# Sheet1.net
KiCad netlist of a schematic drawn in Altium Designer
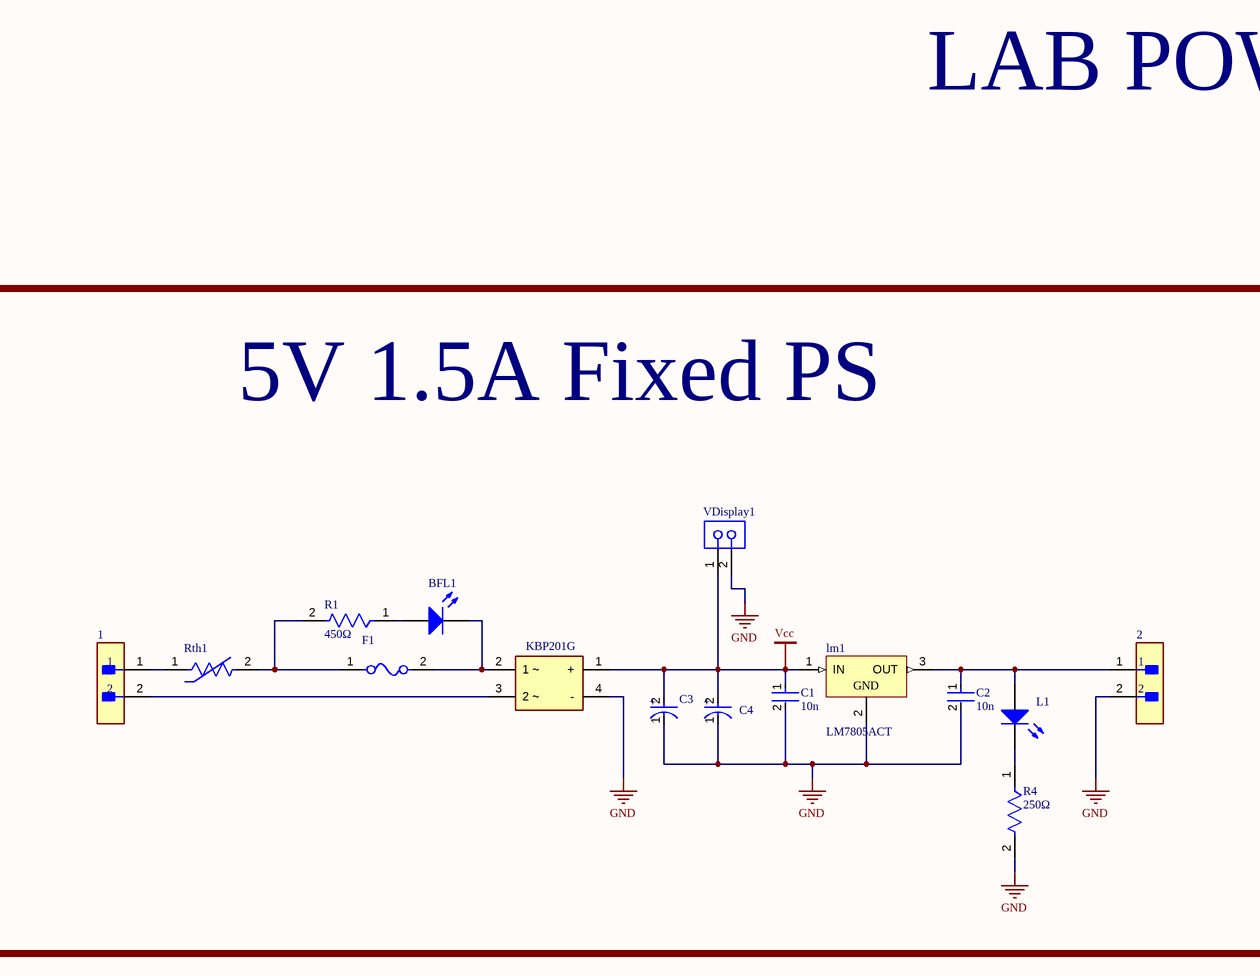
[diagram p0: Sheet1.SchDoc, top left]
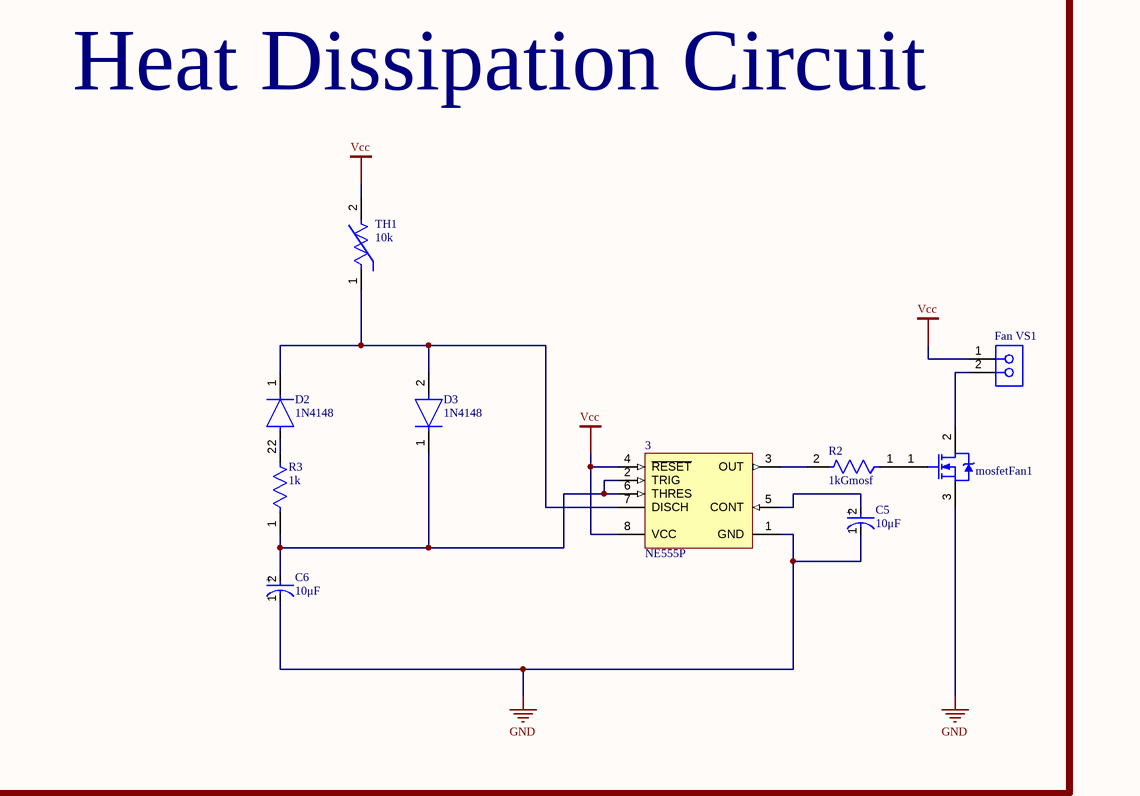
[diagram p1: Sheet1.SchDoc, top right]
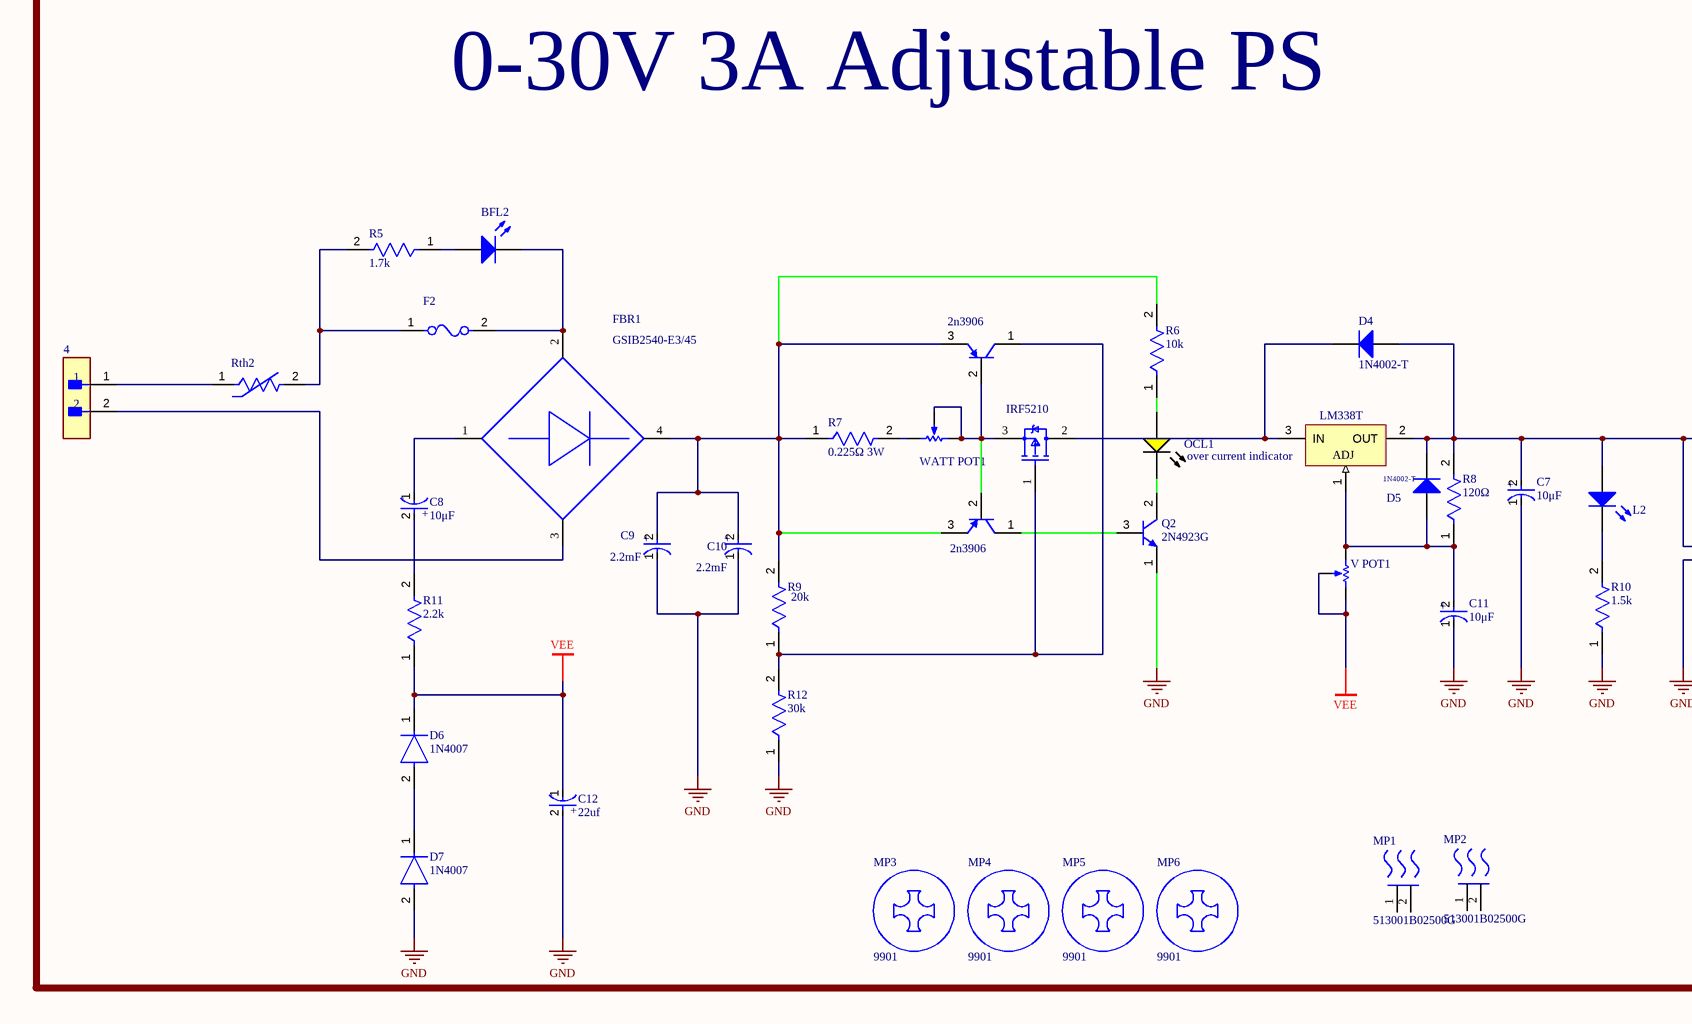
[diagram p2: Sheet1.SchDoc, bottom left]
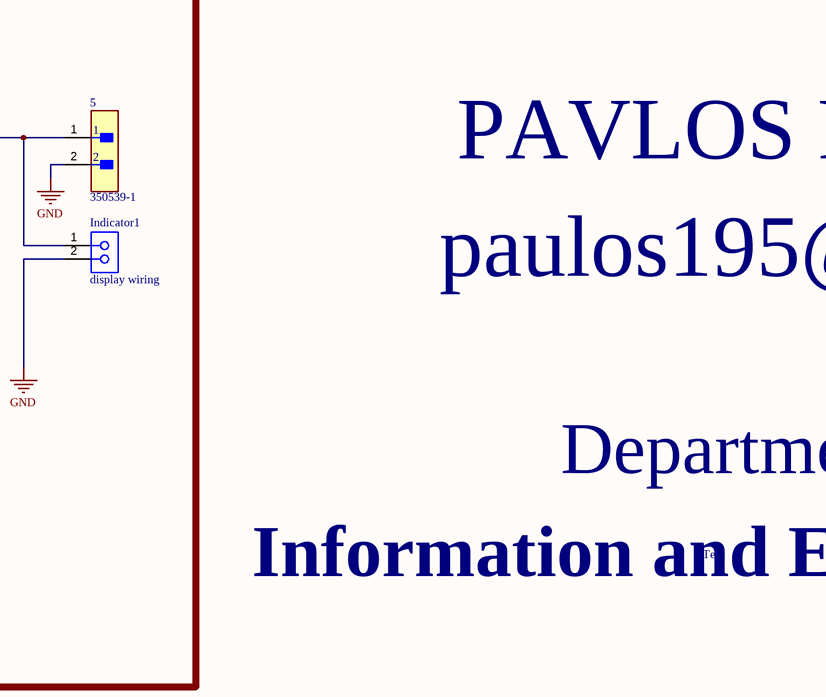
[diagram p3: Sheet1.SchDoc, bottom right]

(export (version "E")
  (design (tool "Eeschema 10.0.6"))
  (components
    (comp (ref "1")
      (value "350539-1")
      (footprint "FP-350539-1-MFG")
      (description "CONN HEADER VERT 2POS 5.08MM")
      (fields
        (field (name "MANUFACTURER") "TE Connectivity")
        (field (name "OCTOPART") "https://octopart.com/350539-1-te+connectivity-46510628")
      )
      (libsource (lib "Altium Content Vault") (part "3bc925449376181038e59eaffc5286c"))
    )
    (comp (ref "2")
      (value "350539-1")
      (footprint "FP-350539-1-MFG")
      (description "CONN HEADER VERT 2POS 5.08MM")
      (fields
        (field (name "MANUFACTURER") "TE Connectivity")
        (field (name "OCTOPART") "https://octopart.com/350539-1-te+connectivity-46510628")
      )
      (libsource (lib "") (part "3bc925449376181038e59eaffc5286c_1"))
    )
    (comp (ref "3")
      (value "NE555P")
      (footprint "P0008A")
      (description "Precision Timer, 4.5 to 16 V, 0 to 70 degC, 8-Pin DIP, Pb-Free, Tube")
      (fields (field (name "MANUFACTURER") "TexasInstruments"))
      (libsource (lib "Altium Content Vault") (part "TI-NE555-P8"))
    )
    (comp (ref "4")
      (value "350539-1")
      (footprint "FP-350539-1-MFG")
      (description "CONN HEADER VERT 2POS 5.08MM")
      (fields
        (field (name "MANUFACTURER") "TE Connectivity")
        (field (name "OCTOPART") "https://octopart.com/350539-1-te+connectivity-46510628")
      )
      (libsource (lib "Altium Content Vault") (part "3bc925449376181038e59eaffc5286c"))
    )
    (comp (ref "5")
      (value "350539-1")
      (footprint "FP-350539-1-MFG")
      (description "CONN HEADER VERT 2POS 5.08MM")
      (fields
        (field (name "MANUFACTURER") "TE Connectivity")
        (field (name "OCTOPART") "https://octopart.com/350539-1-te+connectivity-46510628")
      )
      (libsource (lib "") (part "3bc925449376181038e59eaffc5286c_1"))
    )
    (comp (ref "BFL1")
      (value "Blowfuse indicator")
      (footprint "Type 3mm")
      (description "THT LED round mono-color color lens, WL-TMRW, Super Red")
      (fields (field (name "PARTNUMBER") "151031SS04000") (field (name "MANUFACTURER") "Wuerth Elektronik"))
      (libsource (lib "Altium Content Vault") (part "WE-LED_K1A2-2"))
    )
    (comp (ref "BFL2")
      (value "Blown fuse indicator")
      (footprint "Type 3mm")
      (description "THT LED round mono-color color lens, WL-TMRW, Super Red")
      (fields (field (name "PARTNUMBER") "151031SS04000") (field (name "MANUFACTURER") "Wuerth Elektronik"))
      (libsource (lib "Altium Content Vault") (part "WE-LED_K1A2-2"))
    )
    (comp (ref "C1")
      (value "10n")
      (footprint "FP-RDE0M1-MFG")
      (description "Ceramic Capacitor 100nF ±10% 50V X7R Radial")
      (fields (field (name "TOLERANCE") "10%"))
      (libsource (lib "Altium Content Vault") (part "b4654b650e69147ec39a6b967a45e02"))
    )
    (comp (ref "C2")
      (value "10n")
      (footprint "FP-RDE0M1-MFG")
      (description "Ceramic Capacitor 100nF ±10% 50V X7R Radial")
      (fields (field (name "TOLERANCE") "10%"))
      (libsource (lib "Altium Content Vault") (part "b4654b650e69147ec39a6b967a45e02"))
    )
    (comp (ref "C3")
      (value "2.2mF")
      (footprint "FP-EGPA500ELL222ML40S-MFG")
      (description "CAP ALUM 2200UF 20% 50V RADIAL")
      (fields (field (name "VOLTAGE") "50V") (field (name "TOLERANCE") "20%"))
      (libsource (lib "Altium Content Vault") (part "cf48714ba7e38822c1575c7ec0b6d1f"))
    )
    (comp (ref "C4")
      (value "2.2mF")
      (footprint "FP-EGPA500ELL222ML40S-MFG")
      (description "CAP ALUM 2200UF 20% 50V RADIAL")
      (fields (field (name "VOLTAGE") "50V") (field (name "TOLERANCE") "20%"))
      (libsource (lib "Altium Content Vault") (part "cf48714ba7e38822c1575c7ec0b6d1f"))
    )
    (comp (ref "C5")
      (value "10μF")
      (footprint "FP-ECA-2CHG010I-MFG")
      (description "CAP ALUM 1UF 20% 160V RADIAL")
      (fields (field (name "TOLERANCE") "20%"))
      (libsource (lib "Altium Content Vault") (part "a00bbbee19879c290e62620ae7e47b1"))
    )
    (comp (ref "C6")
      (value "10μF")
      (footprint "FP-ECA-2CHG010I-MFG")
      (description "CAP ALUM 1UF 20% 160V RADIAL")
      (fields (field (name "TOLERANCE") "20%"))
      (libsource (lib "Altium Content Vault") (part "a00bbbee19879c290e62620ae7e47b1"))
    )
    (comp (ref "C7")
      (value "10μF")
      (footprint "FP-ECA-2CHG010I-MFG")
      (description "CAP ALUM 1UF 20% 160V RADIAL")
      (fields (field (name "TOLERANCE") "20%"))
      (libsource (lib "Altium Content Vault") (part "a00bbbee19879c290e62620ae7e47b1"))
    )
    (comp (ref "C8")
      (value "10μF")
      (footprint "FP-ECA-2CHG010I-MFG")
      (description "CAP ALUM 1UF 20% 160V RADIAL")
      (fields (field (name "TOLERANCE") "20%"))
      (libsource (lib "Altium Content Vault") (part "a00bbbee19879c290e62620ae7e47b1"))
    )
    (comp (ref "C9")
      (value "2.2mF")
      (footprint "FP-EGPA500ELL222ML40S-MFG")
      (description "CAP ALUM 2200UF 20% 50V RADIAL")
      (fields (field (name "VOLTAGE") "50V") (field (name "TOLERANCE") "20%"))
      (libsource (lib "Altium Content Vault") (part "cf48714ba7e38822c1575c7ec0b6d1f"))
    )
    (comp (ref "C10")
      (value "2.2mF")
      (footprint "FP-EGPA500ELL222ML40S-MFG")
      (description "CAP ALUM 2200UF 20% 50V RADIAL")
      (fields (field (name "VOLTAGE") "50V") (field (name "TOLERANCE") "20%"))
      (libsource (lib "Altium Content Vault") (part "cf48714ba7e38822c1575c7ec0b6d1f"))
    )
    (comp (ref "C11")
      (value "10μF")
      (footprint "FP-ECA-2CHG010I-MFG")
      (description "CAP ALUM 1UF 20% 160V RADIAL")
      (fields (field (name "TOLERANCE") "20%"))
      (libsource (lib "Altium Content Vault") (part "a00bbbee19879c290e62620ae7e47b1"))
    )
    (comp (ref "C12")
      (value "22uf")
      (footprint "FP-RAD-TH-D_5_0_5-L_7_1-F-MFG")
      (description "Aluminum Electrolytic Capacitors (Radial Lead Type) 33uF ±20% 10V")
      (fields (field (name "TOLERANCE") "20%") (field (name "VOLTAGE") "10V"))
      (libsource (lib "Altium Content Vault") (part "a00bbbee19879c290e62620ae7e47b1"))
    )
    (comp (ref "D1")
      (value "KBP201G")
      (footprint "FP-KBP-MFG")
      (description "BRIDGE RECT 1PHASE 600V 2A KBP")
      (fields
        (field (name "OCTOPART") "https://octopart.com/kbp206g-diodes+inc.-330175")
        (field (name "MANUFACTURER") "Diodes Inc.")
      )
      (libsource (lib "Altium Content Vault") (part "3a1086ec435a8680de2aa37bc9d9ffa"))
    )
    (comp (ref "D2")
      (value "1N4148")
      (footprint "FP-017AG-MFG")
      (description "DIODE GEN PURP 100V 200MA DO35")
      (fields (field (name "VOLTAGE") "100V"))
      (libsource (lib "Altium Content Vault") (part "d7152d700b627762746794eb795d46e"))
    )
    (comp (ref "D3")
      (value "1N4148")
      (footprint "FP-017AG-MFG")
      (description "DIODE GEN PURP 100V 200MA DO35")
      (fields (field (name "VOLTAGE") "100V"))
      (libsource (lib "Altium Content Vault") (part "d7152d700b627762746794eb795d46e"))
    )
    (comp (ref "D4")
      (value "1N4002-T")
      (footprint "DIOD-DO-41-P-2_V")
      (description "1.0 A Rectifier, 15 pF, 100 V, -65 to 150 degC, 2-Pin DO-41 Plastic, RoHS, Tape and Reel")
      (fields (field (name "MANUFACTURER") "Diodes Inc"))
      (libsource (lib "Altium Content Vault") (part "DIOD-D-A1K2-2"))
    )
    (comp (ref "D5")
      (value "1N4002-T")
      (footprint "DIOD-DO-41-P-2_V")
      (description "1.0 A Rectifier, 15 pF, 100 V, -65 to 150 degC, 2-Pin DO-41 Plastic, RoHS, Tape and Reel")
      (fields (field (name "MANUFACTURER") "Diodes Inc"))
      (libsource (lib "Altium Content Vault") (part "DIOD-D-A1K2-2"))
    )
    (comp (ref "D6")
      (value "1N4007")
      (footprint "FP-1N4007-MFG")
      (description "Rectifier diode 1000 V 1 A DO-41, ,")
      (fields
        (field (name "MANUFACTURER") "Diotec")
        (field (name "OCTOPART") "https://octopart.com/1n4007-diotec-4040411")
      )
      (libsource (lib "Altium Content Vault") (part "d7152d700b627762746794eb795d46e"))
    )
    (comp (ref "D7")
      (value "1N4007")
      (footprint "FP-1N4007-MFG")
      (description "Rectifier diode 1000 V 1 A DO-41, ,")
      (fields
        (field (name "MANUFACTURER") "Diotec")
        (field (name "OCTOPART") "https://octopart.com/1n4007-diotec-4040411")
      )
      (libsource (lib "Altium Content Vault") (part "d7152d700b627762746794eb795d46e"))
    )
    (comp (ref "F1")
      (value "64600001223")
      (footprint "FP-64600001223-MFG")
      (description "FUSE BLOCK CART 250V 6.3A PCB")
      (fields
        (field (name "MANUFACTURER") "Littelfuse Inc")
        (field (name "OCTOPART") "https://octopart.com/64600001223-littelfuse-39645661")
      )
      (libsource (lib "Altium Content Vault") (part "5bcf9b9f640e542cf0359d10258e979"))
    )
    (comp (ref "F2")
      (value "64600001223")
      (footprint "FP-64600001223-MFG")
      (description "FUSE BLOCK CART 250V 6.3A PCB")
      (fields
        (field (name "MANUFACTURER") "Littelfuse Inc")
        (field (name "OCTOPART") "https://octopart.com/64600001223-littelfuse-39645661")
      )
      (libsource (lib "Altium Content Vault") (part "5bcf9b9f640e542cf0359d10258e979"))
    )
    (comp (ref "Fan VS1")
      (value "SSQ-102-01-G-S")
      (footprint "SMTC-SSQ-102-01-X-S")
      (description "SQ Post Socket, Through-hole, Vertical, -55 to 125 degC, 2.54 mm Pitch, 2-Pin, Female, RoHS")
      (fields (field (name "MANUFACTURER") "Samtec"))
      (libsource (lib "Altium Content Vault") (part "SMTC-SSQ-102-01-X-S"))
    )
    (comp (ref "FBR1")
      (value "GSIB2540-E3/45")
      (footprint "FP-GSIB2580-E3-45-MFG")
      (description "BRIDGE RECT 1P 800V 3.5A GSIB-5S")
      (fields (field (name "VOLTAGE") "200V"))
      (libsource (lib "Altium Content Vault") (part "51aac32ad35959c46097de5ad95dde1"))
    )
    (comp (ref "Indicator1")
      (value "display wiring")
      (footprint "SMTC-SSQ-102-01-X-S")
      (description "SQ Post Socket, Through-hole, Vertical, -55 to 125 degC, 2.54 mm Pitch, 2-Pin, Female, RoHS")
      (fields (field (name "PARTNUMBER") "SSQ-102-01-G-S") (field (name "MANUFACTURER") "Samtec"))
      (libsource (lib "Altium Content Vault") (part "SMTC-SSQ-102-01-X-S"))
    )
    (comp (ref "L1")
      (value "on indicator")
      (footprint "Type 3mm")
      (description "THT LED round mono-color color lens, WL-TMRC , Bright Green")
      (fields (field (name "PARTNUMBER") "151031VS06000") (field (name "MANUFACTURER") "Wuerth Elektronik"))
      (libsource (lib "Altium Content Vault") (part "WE-LED_K1A2-2"))
    )
    (comp (ref "L2")
      (value "on indicator")
      (footprint "Type 3mm")
      (description "THT LED round mono-color color lens, WL-TMRC , Bright Green")
      (fields (field (name "PARTNUMBER") "151031VS06000") (field (name "MANUFACTURER") "Wuerth Elektronik"))
      (libsource (lib "Altium Content Vault") (part "WE-LED_K1A2-2"))
    )
    (comp (ref "lm1")
      (value "LM7805ACT")
      (footprint "FAIR-TO-220-3")
      (description "Positive Voltage Regulator, 5 V, 1 A, 0 to 125 degC, 3-Pin TO-220, RoHS, Tube")
      (fields (field (name "MANUFACTURER") "Fairchild"))
      (libsource (lib "Altium Content Vault") (part "FAIR-LM7805CT-TO220-3"))
    )
    (comp (ref "LM2")
      (value "LM338T")
      (footprint "NDE0003A")
      (description "5 Amp Adjustable Regulator, 3-pin TO-220, Pb-Free")
      (fields (field (name "MANUFACTURER") "Texas Instruments"))
      (libsource (lib "Altium Content Vault") (part "PM-REG-LM1086ADJ-SIL3"))
    )
    (comp (ref "mosfetCL1")
      (value "IRF5210")
      (footprint "FP-PG-TO262-3-MFG")
      (description "MOSFET P-CH 100V 38A TO262")
      (libsource (lib "Altium Content Vault") (part "6d22d991b1185862a08a901caf23a14"))
    )
    (comp (ref "mosfetFan1")
      (value "IRF3205PBF")
      (footprint "INF-PG-TO-220AB")
      (description "HEXFET(R) Power N-Channel MOSFET, 55 V, 110 A, -55 to 117 degC, 3-Pin TO-220AB, RoHS, Rail/Tube")
      (fields (field (name "MANUFACTURER") "International Rectifier"))
      (libsource (lib "Altium Content Vault") (part "NEMOS-GDS-3_B"))
    )
    (comp (ref "MP1")
      (value "513001B02500G")
      (footprint "FP-513001B02500G-MFG")
      (description "BOARD LEVEL HEAT SINK")
      (libsource (lib "Altium Content Vault") (part "2bc51668f00a2e820a271c5c65feed3"))
    )
    (comp (ref "MP2")
      (value "513001B02500G")
      (footprint "FP-513001B02500G-MFG")
      (description "BOARD LEVEL HEAT SINK")
      (libsource (lib "Altium Content Vault") (part "2bc51668f00a2e820a271c5c65feed3"))
    )
    (comp (ref "MP3")
      (value "9901")
      (footprint "FP-9901-MFG")
      (description "MACHINE SCREW PAN PHILLIPS 4-40")
      (libsource (lib "Altium Content Vault") (part "00aa4b1e0213c22a4cfa0708b50314e"))
    )
    (comp (ref "MP4")
      (value "9901")
      (footprint "FP-9901-MFG")
      (description "MACHINE SCREW PAN PHILLIPS 4-40")
      (libsource (lib "Altium Content Vault") (part "00aa4b1e0213c22a4cfa0708b50314e"))
    )
    (comp (ref "MP5")
      (value "9901")
      (footprint "FP-9901-MFG")
      (description "MACHINE SCREW PAN PHILLIPS 4-40")
      (libsource (lib "Altium Content Vault") (part "00aa4b1e0213c22a4cfa0708b50314e"))
    )
    (comp (ref "MP6")
      (value "9901")
      (footprint "FP-9901-MFG")
      (description "MACHINE SCREW PAN PHILLIPS 4-40")
      (libsource (lib "Altium Content Vault") (part "00aa4b1e0213c22a4cfa0708b50314e"))
    )
    (comp (ref "OCL1")
      (value "over current indicator")
      (footprint "KING-WP7113SYD_V")
      (description "The Super Bright Yellow Device, 2 V, -40 to 85 degC, 2-Pin THD, RoHS, Tape and Reel")
      (fields (field (name "TOLERANCE") "1%"))
      (libsource (lib "Altium Content Vault") (part "LED-YELLOW-AK-2"))
    )
    (comp (ref "Q1")
      (value "2n3906")
      (footprint "ONSC-TO-92-3-29-11_AM_BL")
      (description "Amplifier Transistor, PNP Silicon, 3-Pin TO-92, Pb-Free, Tape and Reel BC557BRL1G")
      (fields (field (name "MANUFACTURER") "On Semiconductor") (field (name "PARTNUMBER") "BC557BRL1G"))
      (libsource (lib "Altium Content Vault") (part "ONSC-PNP-C1B2E3-3"))
    )
    (comp (ref "Q2")
      (value "2N4923G")
      (footprint "ONSC-TO-225-3-77-09")
      (description "Medium-Power Plastic NPN Silicon Transistor, 3-Pin TO-225, Pb-Free, Bulk Box")
      (fields (field (name "MANUFACTURER") "On Semiconductor"))
      (libsource (lib "Altium Content Vault") (part "ONSC-NPN-E1C2B3-3"))
    )
    (comp (ref "Q3")
      (value "2n3906")
      (footprint "ONSC-TO-92-3-29-11_AM_BL")
      (description "Amplifier Transistor, PNP Silicon, 3-Pin TO-92, Pb-Free, Tape and Reel")
      (fields (field (name "MANUFACTURER") "On Semiconductor") (field (name "PARTNUMBER") "BC557BRL1G"))
      (libsource (lib "Altium Content Vault") (part "ONSC-PNP-C1B2E3-3"))
    )
    (comp (ref "R1")
      (value "450Ω")
      (footprint "FP-CF14-MFG")
      (description "RES 7.5K OHM 1/4W 5% AXIAL")
      (fields (field (name "TOLERANCE") "5%"))
      (libsource (lib "Altium Content Vault") (part "1029c3af85768c4190bb7ad29bc67b5"))
    )
    (comp (ref "R2")
      (value "1kGmosf")
      (footprint "FP-CF14-MFG")
      (description "RES 7.5K OHM 1/4W 5% AXIAL")
      (fields (field (name "TOLERANCE") "5%"))
      (libsource (lib "Altium Content Vault") (part "1029c3af85768c4190bb7ad29bc67b5"))
    )
    (comp (ref "R3")
      (value "1k")
      (footprint "FP-CF14-MFG")
      (description "RES 7.5K OHM 1/4W 5% AXIAL")
      (fields (field (name "TOLERANCE") "5%"))
      (libsource (lib "Altium Content Vault") (part "1029c3af85768c4190bb7ad29bc67b5"))
    )
    (comp (ref "R4")
      (value "250Ω")
      (footprint "FP-CF14-MFG")
      (description "RES 7.5K OHM 1/4W 5% AXIAL")
      (fields (field (name "TOLERANCE") "5%"))
      (libsource (lib "Altium Content Vault") (part "1029c3af85768c4190bb7ad29bc67b5"))
    )
    (comp (ref "R5")
      (value "1.7k")
      (footprint "FP-CF14-MFG")
      (description "RES 7.5K OHM 1/4W 5% AXIAL")
      (fields (field (name "TOLERANCE") "5%"))
      (libsource (lib "Altium Content Vault") (part "1029c3af85768c4190bb7ad29bc67b5"))
    )
    (comp (ref "R6")
      (value "10k")
      (footprint "FP-CF14-MFG")
      (description "RES 7.5K OHM 1/4W 5% AXIAL")
      (fields (field (name "TOLERANCE") "5%"))
      (libsource (lib "Altium Content Vault") (part "1029c3af85768c4190bb7ad29bc67b5"))
    )
    (comp (ref "R7")
      (value "0.225Ω 3W")
      (footprint "FP-PAC03-MFG")
      (description "RES 560 OHM 3W 1% AXIAL")
      (fields (field (name "TOLERANCE") "1%"))
      (libsource (lib "Altium Content Vault") (part "1029c3af85768c4190bb7ad29bc67b5"))
    )
    (comp (ref "R8")
      (value "120Ω")
      (footprint "FP-CF14-MFG")
      (description "RES 7.5K OHM 1/4W 5% AXIAL")
      (fields (field (name "TOLERANCE") "5%"))
      (libsource (lib "Altium Content Vault") (part "1029c3af85768c4190bb7ad29bc67b5"))
    )
    (comp (ref "R9")
      (value "20k")
      (footprint "FP-CF14-MFG")
      (description "RES 7.5K OHM 1/4W 5% AXIAL")
      (fields (field (name "TOLERANCE") "5%"))
      (libsource (lib "Altium Content Vault") (part "1029c3af85768c4190bb7ad29bc67b5"))
    )
    (comp (ref "R10")
      (value "1.5k")
      (footprint "FP-CF14-MFG")
      (description "RES 7.5K OHM 1/4W 5% AXIAL")
      (fields (field (name "TOLERANCE") "5%"))
      (libsource (lib "Altium Content Vault") (part "1029c3af85768c4190bb7ad29bc67b5"))
    )
    (comp (ref "R11")
      (value "2.2k")
      (footprint "FP-CF14-MFG")
      (description "RES 7.5K OHM 1/4W 5% AXIAL")
      (fields (field (name "TOLERANCE") "5%"))
      (libsource (lib "Altium Content Vault") (part "1029c3af85768c4190bb7ad29bc67b5"))
    )
    (comp (ref "R12")
      (value "30k")
      (footprint "FP-CF14-MFG")
      (description "RES 7.5K OHM 1/4W 5% AXIAL")
      (fields (field (name "TOLERANCE") "5%"))
      (libsource (lib "Altium Content Vault") (part "1029c3af85768c4190bb7ad29bc67b5"))
    )
    (comp (ref "Rth1")
      (value "NTPAA5R1LDNB0")
      (footprint "FP-NTPAA-MFG")
      (description "ICL 5.1 OHM 15% 2.5A 10MM")
      (fields (field (name "TOLERANCE") "15%") (field (name "VOLTAGE") "264V"))
      (libsource (lib "Altium Content Vault") (part "3b148a6ebabc5fb4d708a66c052d352"))
    )
    (comp (ref "Rth2")
      (value "NTPAA5R1LDNB0")
      (footprint "FP-NTPAA-MFG")
      (description "ICL 5.1 OHM 15% 2.5A 10MM")
      (fields (field (name "TOLERANCE") "15%") (field (name "VOLTAGE") "264V"))
      (libsource (lib "Altium Content Vault") (part "3b148a6ebabc5fb4d708a66c052d352"))
    )
    (comp (ref "TH1")
      (value "10k")
      (footprint "FP-103AT-2-MFG")
      (description "Thermistor NTC 10KOhm 1% 2-Pin")
      (fields (field (name "TOLERANCE") "1%"))
      (libsource (lib "Altium Content Vault") (part "3b148a6ebabc5fb4d708a66c052d352"))
    )
    (comp (ref "V POT1")
      (value "2.85k")
      (footprint "BOUR-3852A-282-103AL-3_V")
      (description "Diameter Panel Control, 10 KOhm, +/- 10%, 2 W, -1 to 125 degC, 3-Pin THD, RoHS, Bulk")
      (fields (field (name "TOLERANCE") "±10%") (field (name "MANUFACTURER") "Bourns"))
      (libsource (lib "Altium Content Vault") (part "RES-POT-3"))
    )
    (comp (ref "VDisplay1")
      (value "SSQ-102-01-G-S")
      (footprint "SMTC-SSQ-102-01-X-S")
      (description "SQ Post Socket, Through-hole, Vertical, -55 to 125 degC, 2.54 mm Pitch, 2-Pin, Female, RoHS")
      (fields (field (name "MANUFACTURER") "Samtec"))
      (libsource (lib "Altium Content Vault") (part "SMTC-SSQ-102-01-X-S"))
    )
    (comp (ref "WATT POT1")
      (value "3852A-282-103AL")
      (footprint "BOUR-3852A-282-103AL-3_V")
      (description "Diameter Panel Control, 10 KOhm, +/- 10%, 2 W, -1 to 125 degC, 3-Pin THD, RoHS, Bulk")
      (fields (field (name "TOLERANCE") "±10%") (field (name "MANUFACTURER") "Bourns"))
      (libsource (lib "Altium Content Vault") (part "RES-POT-3"))
    )
  )
  (nets
    (net (code "1") (name "GND") (class "Default")
      (node (ref "2") (pin "2") (pinfunction "2_2") (pintype "passive"))
      (node (ref "3") (pin "1") (pinfunction "GND_1") (pintype "power_in"))
      (node (ref "5") (pin "2") (pinfunction "2_2") (pintype "passive"))
      (node (ref "C1") (pin "2") (pinfunction "2_2") (pintype "passive"))
      (node (ref "C10") (pin "1") (pinfunction "C_1") (pintype "passive"))
      (node (ref "C11") (pin "1") (pinfunction "C_1") (pintype "passive"))
      (node (ref "C12") (pin "2") (pinfunction "A_2") (pintype "passive"))
      (node (ref "C2") (pin "2") (pinfunction "2_2") (pintype "passive"))
      (node (ref "C3") (pin "1") (pinfunction "C_1") (pintype "passive"))
      (node (ref "C4") (pin "1") (pinfunction "C_1") (pintype "passive"))
      (node (ref "C5") (pin "1") (pinfunction "C_1") (pintype "passive"))
      (node (ref "C6") (pin "1") (pinfunction "C_1") (pintype "passive"))
      (node (ref "C7") (pin "1") (pinfunction "C_1") (pintype "passive"))
      (node (ref "C9") (pin "1") (pinfunction "C_1") (pintype "passive"))
      (node (ref "D1") (pin "4") (pinfunction "-_4") (pintype "passive"))
      (node (ref "D7") (pin "2") (pinfunction "A_2") (pintype "passive"))
      (node (ref "Indicator1") (pin "2") (pinfunction "2_2") (pintype "passive"))
      (node (ref "Q2") (pin "1") (pinfunction "E_1") (pintype "passive"))
      (node (ref "R10") (pin "1") (pinfunction "1_1") (pintype "passive"))
      (node (ref "R12") (pin "1") (pinfunction "1_1") (pintype "passive"))
      (node (ref "R4") (pin "2") (pinfunction "2_2") (pintype "passive"))
      (node (ref "VDisplay1") (pin "2") (pinfunction "2_2") (pintype "passive"))
      (node (ref "lm1") (pin "2") (pinfunction "GND_2") (pintype "power_in"))
      (node (ref "mosfetFan1") (pin "3") (pinfunction "S_3") (pintype "passive"))
    )
    (net (code "2") (name "Net-(1-Pad1)") (class "Default")
      (node (ref "1") (pin "1") (pinfunction "1_1") (pintype "passive"))
      (node (ref "Rth1") (pin "1") (pinfunction "1_1") (pintype "passive"))
    )
    (net (code "3") (name "Net-(3-CONT)") (class "Default")
      (node (ref "3") (pin "5") (pinfunction "CONT_5") (pintype "input"))
      (node (ref "C5") (pin "2") (pinfunction "A_2") (pintype "passive"))
    )
    (net (code "4") (name "Net-(3-DISCH)") (class "Default")
      (node (ref "3") (pin "7") (pinfunction "DISCH_7") (pintype "open_collector"))
      (node (ref "D2") (pin "1") (pinfunction "C_1") (pintype "passive"))
      (node (ref "D3") (pin "2") (pinfunction "A_2") (pintype "passive"))
      (node (ref "TH1") (pin "1") (pinfunction "1_1") (pintype "passive"))
    )
    (net (code "5") (name "Net-(3-OUT)") (class "Default")
      (node (ref "3") (pin "3") (pinfunction "OUT_3") (pintype "output"))
      (node (ref "R2") (pin "2") (pinfunction "2_2") (pintype "passive"))
    )
    (net (code "6") (name "Net-(3-THRES)") (class "Default")
      (node (ref "3") (pin "2") (pinfunction "TRIG_2") (pintype "input"))
      (node (ref "3") (pin "6") (pinfunction "THRES_6") (pintype "input"))
      (node (ref "C6") (pin "2") (pinfunction "A_2") (pintype "passive"))
      (node (ref "D3") (pin "1") (pinfunction "C_1") (pintype "passive"))
      (node (ref "R3") (pin "1") (pinfunction "1_1") (pintype "passive"))
    )
    (net (code "7") (name "Net-(4-Pad1)") (class "Default")
      (node (ref "4") (pin "1") (pinfunction "1_1") (pintype "passive"))
      (node (ref "Rth2") (pin "1") (pinfunction "1_1") (pintype "passive"))
    )
    (net (code "8") (name "Net-(BFL1-A)") (class "Default")
      (node (ref "BFL1") (pin "2") (pinfunction "A_2") (pintype "passive"))
      (node (ref "R1") (pin "1") (pinfunction "1_1") (pintype "passive"))
    )
    (net (code "9") (name "Net-(BFL1-K)") (class "Default")
      (node (ref "BFL1") (pin "1") (pinfunction "K_1") (pintype "passive"))
      (node (ref "D1") (pin "2") (pinfunction "1_~_2") (pintype "passive"))
      (node (ref "F1") (pin "2") (pinfunction "2_2") (pintype "passive"))
    )
    (net (code "10") (name "Net-(BFL2-A)") (class "Default")
      (node (ref "BFL2") (pin "2") (pinfunction "A_2") (pintype "passive"))
      (node (ref "R5") (pin "1") (pinfunction "1_1") (pintype "passive"))
    )
    (net (code "11") (name "Net-(BFL2-K)") (class "Default")
      (node (ref "BFL2") (pin "1") (pinfunction "K_1") (pintype "passive"))
      (node (ref "F2") (pin "2") (pinfunction "2_2") (pintype "passive"))
      (node (ref "FBR1") (pin "2") (pinfunction "1_~_2") (pintype "passive"))
    )
    (net (code "12") (name "Net-(C7-A)") (class "Default")
      (node (ref "5") (pin "1") (pinfunction "1_1") (pintype "passive"))
      (node (ref "C7") (pin "2") (pinfunction "A_2") (pintype "passive"))
      (node (ref "D4") (pin "1") (pinfunction "A_1") (pintype "passive"))
      (node (ref "D5") (pin "2") (pinfunction "K_2") (pintype "passive"))
      (node (ref "Indicator1") (pin "1") (pinfunction "1_1") (pintype "passive"))
      (node (ref "L2") (pin "2") (pinfunction "A_2") (pintype "passive"))
      (node (ref "LM2") (pin "2") (pinfunction "OUT_2") (pintype "power_in"))
      (node (ref "R8") (pin "2") (pinfunction "2_2") (pintype "passive"))
    )
    (net (code "13") (name "Net-(C8-A)") (class "Default")
      (node (ref "C8") (pin "2") (pinfunction "A_2") (pintype "passive"))
      (node (ref "R11") (pin "2") (pinfunction "2_2") (pintype "passive"))
    )
    (net (code "14") (name "Net-(C8-C)") (class "Default")
      (node (ref "C8") (pin "1") (pinfunction "C_1") (pintype "passive"))
      (node (ref "FBR1") (pin "1") (pinfunction "+_1") (pintype "passive"))
    )
    (net (code "15") (name "Net-(C10-A)") (class "Default")
      (node (ref "C10") (pin "2") (pinfunction "A_2") (pintype "passive"))
      (node (ref "C9") (pin "2") (pinfunction "A_2") (pintype "passive"))
      (node (ref "FBR1") (pin "4") (pinfunction "-_4") (pintype "passive"))
      (node (ref "Q1") (pin "3") (pinfunction "E_3") (pintype "passive"))
      (node (ref "Q3") (pin "3") (pinfunction "E_3") (pintype "passive"))
      (node (ref "R6") (pin "2") (pinfunction "2_2") (pintype "passive"))
      (node (ref "R7") (pin "1") (pinfunction "1_1") (pintype "passive"))
      (node (ref "R9") (pin "2") (pinfunction "2_2") (pintype "passive"))
    )
    (net (code "16") (name "Net-(C11-A)") (class "Default")
      (node (ref "C11") (pin "2") (pinfunction "A_2") (pintype "passive"))
      (node (ref "D5") (pin "1") (pinfunction "A_1") (pintype "passive"))
      (node (ref "LM2") (pin "1") (pinfunction "ADJ_1") (pintype "input"))
      (node (ref "R8") (pin "1") (pinfunction "1_1") (pintype "passive"))
      (node (ref "V POT1") (pin "1") (pinfunction "CCW_1") (pintype "passive"))
    )
    (net (code "17") (name "Net-(D1-2_~)") (class "Default")
      (node (ref "1") (pin "2") (pinfunction "2_2") (pintype "passive"))
      (node (ref "D1") (pin "3") (pinfunction "2_~_3") (pintype "passive"))
    )
    (net (code "18") (name "Net-(D2-A)") (class "Default")
      (node (ref "D2") (pin "2") (pinfunction "A_2") (pintype "passive"))
      (node (ref "R3") (pin "2") (pinfunction "2_2") (pintype "passive"))
    )
    (net (code "19") (name "Net-(D4-K)") (class "Default")
      (node (ref "D4") (pin "2") (pinfunction "K_2") (pintype "passive"))
      (node (ref "LM2") (pin "3") (pinfunction "IN_3") (pintype "power_in"))
      (node (ref "mosfetCL1") (pin "2") (pinfunction "Drain_2") (pintype "passive"))
    )
    (net (code "20") (name "Net-(D6-A)") (class "Default")
      (node (ref "D6") (pin "2") (pinfunction "A_2") (pintype "passive"))
      (node (ref "D7") (pin "1") (pinfunction "C_1") (pintype "passive"))
    )
    (net (code "21") (name "Net-(F1-Pad1)") (class "Default")
      (node (ref "F1") (pin "1") (pinfunction "1_1") (pintype "passive"))
      (node (ref "R1") (pin "2") (pinfunction "2_2") (pintype "passive"))
      (node (ref "Rth1") (pin "2") (pinfunction "2_2") (pintype "passive"))
    )
    (net (code "22") (name "Net-(F2-Pad1)") (class "Default")
      (node (ref "F2") (pin "1") (pinfunction "1_1") (pintype "passive"))
      (node (ref "R5") (pin "2") (pinfunction "2_2") (pintype "passive"))
      (node (ref "Rth2") (pin "2") (pinfunction "2_2") (pintype "passive"))
    )
    (net (code "23") (name "Net-(FBR1-2_~)") (class "Default")
      (node (ref "4") (pin "2") (pinfunction "2_2") (pintype "passive"))
      (node (ref "FBR1") (pin "3") (pinfunction "2_~_3") (pintype "passive"))
    )
    (net (code "24") (name "Net-(L1-A)") (class "Default")
      (node (ref "2") (pin "1") (pinfunction "1_1") (pintype "passive"))
      (node (ref "C2") (pin "1") (pinfunction "1_1") (pintype "passive"))
      (node (ref "L1") (pin "2") (pinfunction "A_2") (pintype "passive"))
      (node (ref "lm1") (pin "3") (pinfunction "OUT_3") (pintype "output"))
    )
    (net (code "25") (name "Net-(L1-K)") (class "Default")
      (node (ref "L1") (pin "1") (pinfunction "K_1") (pintype "passive"))
      (node (ref "R4") (pin "1") (pinfunction "1_1") (pintype "passive"))
    )
    (net (code "26") (name "Net-(L2-K)") (class "Default")
      (node (ref "L2") (pin "1") (pinfunction "K_1") (pintype "passive"))
      (node (ref "R10") (pin "2") (pinfunction "2_2") (pintype "passive"))
    )
    (net (code "27") (name "Net-(OCL1-A)") (class "Default")
      (node (ref "OCL1") (pin "1") (pinfunction "A_1") (pintype "passive"))
      (node (ref "R6") (pin "1") (pinfunction "1_1") (pintype "passive"))
    )
    (net (code "28") (name "Net-(OCL1-K)") (class "Default")
      (node (ref "OCL1") (pin "2") (pinfunction "K_2") (pintype "passive"))
      (node (ref "Q2") (pin "2") (pinfunction "C_2") (pintype "passive"))
    )
    (net (code "29") (name "Net-(Q1-B)") (class "Default")
      (node (ref "Q1") (pin "2") (pinfunction "B_2") (pintype "passive"))
      (node (ref "Q3") (pin "2") (pinfunction "B_2") (pintype "passive"))
      (node (ref "WATT POT1") (pin "1") (pinfunction "CCW_1") (pintype "passive"))
      (node (ref "WATT POT1") (pin "2") (pinfunction "S_2") (pintype "passive"))
      (node (ref "mosfetCL1") (pin "3") (pinfunction "Source_3") (pintype "passive"))
    )
    (net (code "30") (name "Net-(Q1-C)") (class "Default")
      (node (ref "Q1") (pin "1") (pinfunction "C_1") (pintype "passive"))
      (node (ref "R12") (pin "2") (pinfunction "2_2") (pintype "passive"))
      (node (ref "R9") (pin "1") (pinfunction "1_1") (pintype "passive"))
      (node (ref "mosfetCL1") (pin "1") (pinfunction "Gate_1") (pintype "passive"))
    )
    (net (code "31") (name "Net-(Q2-B)") (class "Default")
      (node (ref "Q2") (pin "3") (pinfunction "B_3") (pintype "passive"))
      (node (ref "Q3") (pin "1") (pinfunction "C_1") (pintype "passive"))
    )
    (net (code "32") (name "Net-(WATT POT1-CW)") (class "Default")
      (node (ref "R7") (pin "2") (pinfunction "2_2") (pintype "passive"))
      (node (ref "WATT POT1") (pin "3") (pinfunction "CW_3") (pintype "passive"))
    )
    (net (code "33") (name "Net-(mosfetFan1-D)") (class "Default")
      (node (ref "Fan VS1") (pin "2") (pinfunction "2_2") (pintype "passive"))
      (node (ref "mosfetFan1") (pin "2") (pinfunction "D_2") (pintype "passive"))
    )
    (net (code "34") (name "Net-(mosfetFan1-G)") (class "Default")
      (node (ref "R2") (pin "1") (pinfunction "1_1") (pintype "passive"))
      (node (ref "mosfetFan1") (pin "1") (pinfunction "G_1") (pintype "passive"))
    )
    (net (code "35") (name "VEE") (class "Default")
      (node (ref "C12") (pin "1") (pinfunction "C_1") (pintype "passive"))
      (node (ref "D6") (pin "1") (pinfunction "C_1") (pintype "passive"))
      (node (ref "R11") (pin "1") (pinfunction "1_1") (pintype "passive"))
      (node (ref "V POT1") (pin "2") (pinfunction "S_2") (pintype "passive"))
      (node (ref "V POT1") (pin "3") (pinfunction "CW_3") (pintype "passive"))
    )
    (net (code "36") (name "Vcc") (class "Default")
      (node (ref "3") (pin "4") (pinfunction "~{RESET}_4") (pintype "input"))
      (node (ref "3") (pin "8") (pinfunction "VCC_8") (pintype "power_in"))
      (node (ref "C1") (pin "1") (pinfunction "1_1") (pintype "passive"))
      (node (ref "C3") (pin "2") (pinfunction "A_2") (pintype "passive"))
      (node (ref "C4") (pin "2") (pinfunction "A_2") (pintype "passive"))
      (node (ref "D1") (pin "1") (pinfunction "+_1") (pintype "passive"))
      (node (ref "Fan VS1") (pin "1") (pinfunction "1_1") (pintype "passive"))
      (node (ref "TH1") (pin "2") (pinfunction "2_2") (pintype "passive"))
      (node (ref "VDisplay1") (pin "1") (pinfunction "1_1") (pintype "passive"))
      (node (ref "lm1") (pin "1") (pinfunction "IN_1") (pintype "input"))
    )
    (net (code "37") (name "unconnected-(MP1-MNT_1-Pad1)") (class "Default")
      (node (ref "MP1") (pin "1") (pinfunction "MNT_1_1") (pintype "passive"))
    )
    (net (code "38") (name "unconnected-(MP1-MNT_2-Pad2)") (class "Default")
      (node (ref "MP1") (pin "2") (pinfunction "MNT_2_2") (pintype "passive"))
    )
    (net (code "39") (name "unconnected-(MP2-MNT_1-Pad1)") (class "Default")
      (node (ref "MP2") (pin "1") (pinfunction "MNT_1_1") (pintype "passive"))
    )
    (net (code "40") (name "unconnected-(MP2-MNT_2-Pad2)") (class "Default")
      (node (ref "MP2") (pin "2") (pinfunction "MNT_2_2") (pintype "passive"))
    )
  )
)
